# GMM_TESTER_PA_Sheet1.net
KiCad netlist of a schematic drawn in Altium Designer
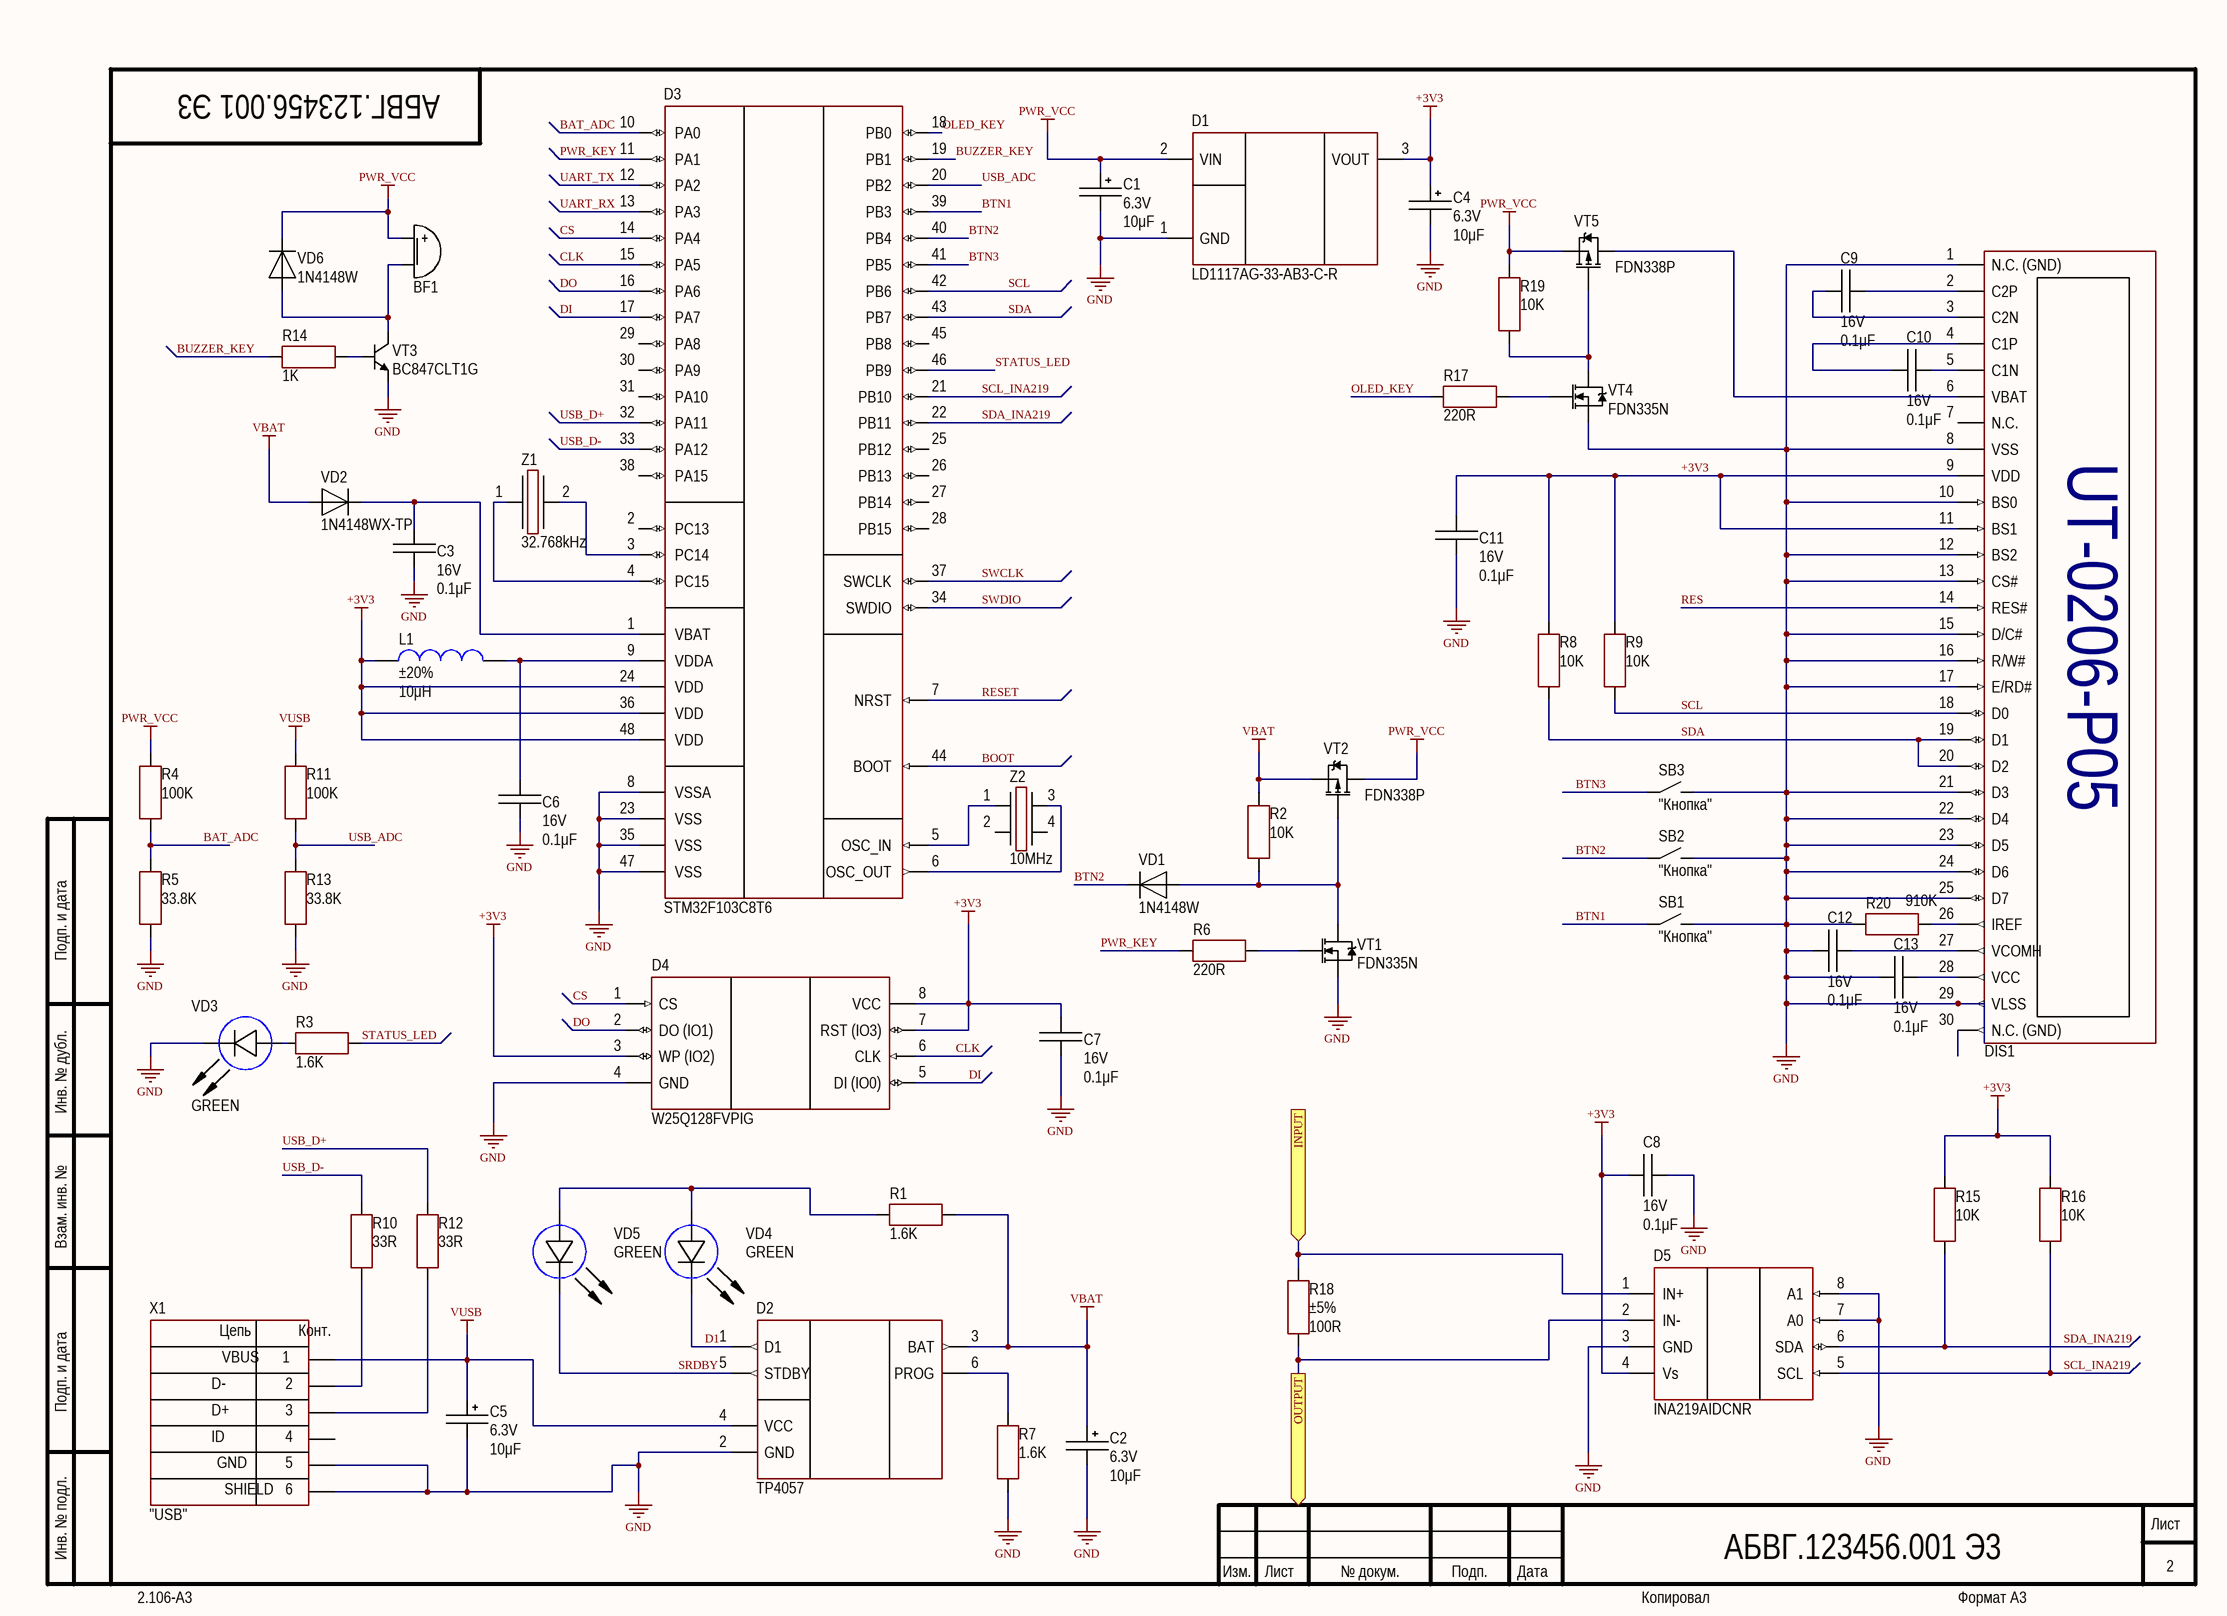
[diagram p0: GMM_TESTER_PA_Sheet1.SchDoc]

(export (version "E")
  (design (tool "Eeschema 10.0.6"))
  (components
    (comp (ref "BF1")
      (value "~")
      (footprint "CustomCase:BUZ: CMT-7525")
      (fields
        (field (name "MANUFACTURER") "PUI Audio")
        (field (name "VALUEMANUFACTURERPARTNUMBER") "DIP switch, 2.73 kHz, 3VDC, 80mA, -20...+70°C")
        (field (name "PARTNUMBER") "AT-0927-TT-6-R")
      )
      (libsource (lib "Electromechanics") (part "Buzzer"))
    )
    (comp (ref "C1")
      (value "10μF")
      (footprint "StandardCase:CAP: TANTAL-A")
      (fields
        (field (name "MANUFACTURER") "AVX")
        (field (name "PARTNUMBER") "F930J107KAAAJ6")
        (field (name "VALUEMANUFACTURERPARTNUMBER") "Tantalum capacitor, 10μF, 6.3V, ±10%, 2Ohm, case A (3216), -55...+125°C")
        (field (name "VOLTAGE") "6.3V")
      )
      (libsource (lib "Capacitor") (part "Tantal_A"))
    )
    (comp (ref "C2")
      (value "10μF")
      (footprint "StandardCase:CAP: TANTAL-A")
      (fields
        (field (name "MANUFACTURER") "AVX")
        (field (name "PARTNUMBER") "F930J107KAAAJ6")
        (field (name "VALUEMANUFACTURERPARTNUMBER") "Tantalum capacitor, 10μF, 6.3V, ±10%, 2Ohm, case A (3216), -55...+125°C")
        (field (name "VOLTAGE") "6.3V")
      )
      (libsource (lib "Capacitor") (part "Tantal_A"))
    )
    (comp (ref "C3")
      (value "0.1μF")
      (footprint "StandardCase:CAP: 0603")
      (fields
        (field (name "MANUFACTURER") "Yageo")
        (field (name "PARTNUMBER") "CC0603KRX7R7BB104")
        (field (name "VALUEMANUFACTURERPARTNUMBER") "Ceramic capacitor, 0.1μF, X7R, ±10%, 16V, 0603, -55...+125°C")
        (field (name "VOLTAGE") "16V")
      )
      (libsource (lib "Capacitor") (part "Ceramic_0603"))
    )
    (comp (ref "C4")
      (value "10μF")
      (footprint "StandardCase:CAP: TANTAL-A")
      (fields
        (field (name "MANUFACTURER") "AVX")
        (field (name "PARTNUMBER") "F930J107KAAAJ6")
        (field (name "VALUEMANUFACTURERPARTNUMBER") "Tantalum capacitor, 10μF, 6.3V, ±10%, 2Ohm, case A (3216), -55...+125°C")
        (field (name "VOLTAGE") "6.3V")
      )
      (libsource (lib "Capacitor") (part "Tantal_A"))
    )
    (comp (ref "C5")
      (value "10μF")
      (footprint "StandardCase:CAP: TANTAL-A")
      (fields
        (field (name "MANUFACTURER") "AVX")
        (field (name "PARTNUMBER") "F930J107KAAAJ6")
        (field (name "VALUEMANUFACTURERPARTNUMBER") "Tantalum capacitor, 10μF, 6.3V, ±10%, 2Ohm, case A (3216), -55...+125°C")
        (field (name "VOLTAGE") "6.3V")
      )
      (libsource (lib "Capacitor") (part "Tantal_A"))
    )
    (comp (ref "C6")
      (value "0.1μF")
      (footprint "StandardCase:CAP: 0603")
      (fields
        (field (name "MANUFACTURER") "Yageo")
        (field (name "PARTNUMBER") "CC0603KRX7R7BB104")
        (field (name "VALUEMANUFACTURERPARTNUMBER") "Ceramic capacitor, 0.1μF, X7R, ±10%, 16V, 0603, -55...+125°C")
        (field (name "VOLTAGE") "16V")
      )
      (libsource (lib "Capacitor") (part "Ceramic_0603"))
    )
    (comp (ref "C7")
      (value "0.1μF")
      (footprint "StandardCase:CAP: 0603")
      (fields
        (field (name "MANUFACTURER") "Yageo")
        (field (name "PARTNUMBER") "CC0603KRX7R7BB104")
        (field (name "VALUEMANUFACTURERPARTNUMBER") "Ceramic capacitor, 0.1μF, X7R, ±10%, 16V, 0603, -55...+125°C")
        (field (name "VOLTAGE") "16V")
      )
      (libsource (lib "Capacitor") (part "Ceramic_0603"))
    )
    (comp (ref "C8")
      (value "0.1μF")
      (footprint "StandardCase:CAP: 0603")
      (fields
        (field (name "MANUFACTURER") "Yageo")
        (field (name "PARTNUMBER") "CC0603KRX7R7BB104")
        (field (name "VALUEMANUFACTURERPARTNUMBER") "Ceramic capacitor, 0.1μF, X7R, ±10%, 16V, 0603, -55...+125°C")
        (field (name "VOLTAGE") "16V")
      )
      (libsource (lib "Capacitor") (part "Ceramic_0603"))
    )
    (comp (ref "C9")
      (value "0.1μF")
      (footprint "StandardCase:CAP: 0603")
      (fields
        (field (name "MANUFACTURER") "Yageo")
        (field (name "PARTNUMBER") "CC0603KRX7R7BB104")
        (field (name "VALUEMANUFACTURERPARTNUMBER") "Ceramic capacitor, 0.1μF, X7R, ±10%, 16V, 0603, -55...+125°C")
        (field (name "VOLTAGE") "16V")
      )
      (libsource (lib "Capacitor") (part "Ceramic_0603"))
    )
    (comp (ref "C10")
      (value "0.1μF")
      (footprint "StandardCase:CAP: 0603")
      (fields
        (field (name "MANUFACTURER") "Yageo")
        (field (name "PARTNUMBER") "CC0603KRX7R7BB104")
        (field (name "VALUEMANUFACTURERPARTNUMBER") "Ceramic capacitor, 0.1μF, X7R, ±10%, 16V, 0603, -55...+125°C")
        (field (name "VOLTAGE") "16V")
      )
      (libsource (lib "Capacitor") (part "Ceramic_0603"))
    )
    (comp (ref "C11")
      (value "0.1μF")
      (footprint "StandardCase:CAP: 0603")
      (fields
        (field (name "MANUFACTURER") "Yageo")
        (field (name "PARTNUMBER") "CC0603KRX7R7BB104")
        (field (name "VALUEMANUFACTURERPARTNUMBER") "Ceramic capacitor, 0.1μF, X7R, ±10%, 16V, 0603, -55...+125°C")
        (field (name "VOLTAGE") "16V")
      )
      (libsource (lib "Capacitor") (part "Ceramic_0603"))
    )
    (comp (ref "C12")
      (value "0.1μF")
      (footprint "StandardCase:CAP: 0603")
      (fields
        (field (name "MANUFACTURER") "Yageo")
        (field (name "PARTNUMBER") "CC0603KRX7R7BB104")
        (field (name "VALUEMANUFACTURERPARTNUMBER") "Ceramic capacitor, 0.1μF, X7R, ±10%, 16V, 0603, -55...+125°C")
        (field (name "VOLTAGE") "16V")
      )
      (libsource (lib "Capacitor") (part "Ceramic_0603"))
    )
    (comp (ref "C13")
      (value "0.1μF")
      (footprint "StandardCase:CAP: 0603")
      (fields
        (field (name "MANUFACTURER") "Yageo")
        (field (name "PARTNUMBER") "CC0603KRX7R7BB104")
        (field (name "VALUEMANUFACTURERPARTNUMBER") "Ceramic capacitor, 0.1μF, X7R, ±10%, 16V, 0603, -55...+125°C")
        (field (name "VOLTAGE") "16V")
      )
      (libsource (lib "Capacitor") (part "Ceramic_0603"))
    )
    (comp (ref "D1")
      (value "~")
      (footprint "SOT89")
      (description "Linear voltage regulator")
      (fields
        (field (name "MANUFACTURER") "STMicroelectronics")
        (field (name "VALUEMANUFACTURERPARTNUMBER") "Linear voltage regulator, input 3.9...18V, 0.6V, output 3.3V, 1.2A, -40...+85°C, SOT89")
        (field (name "PARTNUMBER") "LD1117AG-33-AB3-C-R")
      )
      (libsource (lib "IC. Power supply") (part "LD1117AG-33-AB3-C-R"))
    )
    (comp (ref "D2")
      (value "~")
      (footprint "StandardCase:SOT23-6")
      (description "500mA Linear Li-Ion Battery Charger")
      (fields
        (field (name "MANUFACTURER") "Texas Instruments")
        (field (name "VALUEMANUFACTURERPARTNUMBER") "DC/DC push-pull converter, input 2.25...5.5V, 160kHz, , 500ma, -55...+125°C, SOT23-6")
        (field (name "PARTNUMBER") "TP4057")
      )
      (libsource (lib "IC. Power supply") (part "TP4057"))
    )
    (comp (ref "D3")
      (value "~")
      (footprint "StandardCase:48-LQFP")
      (description "Cortex-M3")
      (fields
        (field (name "MANUFACTURER") "STMicroelectronics")
        (field (name "VALUEMANUFACTURERPARTNUMBER") "IC microcontroller, 32-Bit, Cortex-M3, 72MHz, 64KB, 20KB, 2...3.6V, -40...+85°C, 48-LQFP")
        (field (name "PARTNUMBER") "STM32F103C8T6")
      )
      (libsource (lib "IC. MCU") (part "STM32F103C8T6"))
    )
    (comp (ref "D4")
      (value "~")
      (footprint "StandardCase:8-SOIC")
      (description "FLASH")
      (fields
        (field (name "MANUFACTURER") "Winbond Electronics")
        (field (name "VALUEMANUFACTURERPARTNUMBER") "IC memory, FLASH, 128Mb (16M x 8), 104 MHz, SPI/QuadSPI, 2.7...3.6V, -40...+85°C, 8-WSON")
        (field (name "PARTNUMBER") "W25Q128FVPIG")
      )
      (libsource (lib "IC. Memory") (part "W25Q128FVPIG"))
    )
    (comp (ref "D5")
      (value "~")
      (footprint "SOT23-8")
      (description "Current monitor")
      (fields
        (field (name "MANUFACTURER") "Texas Instruments")
        (field (name "VALUEMANUFACTURERPARTNUMBER") "IC current monitor, ±3%, 350 kHz, 2.7...5.5V, -40...+125°C, SOT23-6")
        (field (name "PARTNUMBER") "INA219AIDCNR")
      )
      (libsource (lib "IC. Sensor") (part "INA219AIDCNR"))
    )
    (comp (ref "DIS1")
      (value "~")
      (footprint "DISP: OLED UT-0206-P05")
      (fields
        (field (name "MANUFACTURER") "Shenzhen Allvision Tech")
        (field (name "VALUEMANUFACTURERPARTNUMBER") "QG-2864KSWEG01, , 5VDC, , -40...+85°C")
      )
      (libsource (lib "Displays") (part "QG-2864KSWEG01"))
    )
    (comp (ref "L1")
      (value "10μH")
      (footprint "StandardCase:IND: 0603")
      (fields
        (field (name "MANUFACTURER") "Murata Electronics")
        (field (name "PARTNUMBER") "LQM18FN100M00D")
        (field (name "VALUEMANUFACTURERPARTNUMBER") "Fixed inductor, 10μH, ±20%, 0603, 50mA, -55...+125°C")
        (field (name "TOLERANCE") "±20%")
      )
      (libsource (lib "Inductor") (part "Inductor_0603"))
    )
    (comp (ref "R1")
      (value "1.6K")
      (footprint "StandardCase:RES: 0603")
      (fields
        (field (name "MANUFACTURER") "Yageo")
        (field (name "PARTNUMBER") "RC0603JR-07100RL")
        (field (name "VALUEMANUFACTURERPARTNUMBER") "Resistor film, 1.6K, , 0603, 0.1W, -55...+125°C")
      )
      (libsource (lib "Resistor") (part "Resistor_0603"))
    )
    (comp (ref "R2")
      (value "10K")
      (footprint "StandardCase:RES: 0603")
      (fields
        (field (name "MANUFACTURER") "Yageo")
        (field (name "PARTNUMBER") "RC0603JR-07100RL")
        (field (name "VALUEMANUFACTURERPARTNUMBER") "Resistor film, 10K, , 0603, 0.1W, -55...+125°C")
      )
      (libsource (lib "") (part "Resistor_0603_1"))
    )
    (comp (ref "R3")
      (value "1.6K")
      (footprint "StandardCase:RES: 0603")
      (fields
        (field (name "MANUFACTURER") "Yageo")
        (field (name "PARTNUMBER") "RC0603JR-07100RL")
        (field (name "VALUEMANUFACTURERPARTNUMBER") "Resistor film, 1.6K, , 0603, 0.1W, -55...+125°C")
      )
      (libsource (lib "Resistor") (part "Resistor_0603"))
    )
    (comp (ref "R4")
      (value "100K")
      (footprint "StandardCase:RES: 0603")
      (fields
        (field (name "MANUFACTURER") "Yageo")
        (field (name "PARTNUMBER") "RC0603JR-07100RL")
        (field (name "VALUEMANUFACTURERPARTNUMBER") "Resistor film, 100K, , 0603, 0.1W, -55...+125°C")
      )
      (libsource (lib "") (part "Resistor_0603_1"))
    )
    (comp (ref "R5")
      (value "33.8K")
      (footprint "StandardCase:RES: 0603")
      (fields
        (field (name "MANUFACTURER") "Yageo")
        (field (name "PARTNUMBER") "RC0603JR-07100RL")
        (field (name "VALUEMANUFACTURERPARTNUMBER") "Resistor film, 33.8K, , 0603, 0.1W, -55...+125°C")
      )
      (libsource (lib "") (part "Resistor_0603_1"))
    )
    (comp (ref "R6")
      (value "220R")
      (footprint "StandardCase:RES: 0603")
      (fields
        (field (name "MANUFACTURER") "Yageo")
        (field (name "PARTNUMBER") "RC0603JR-07100RL")
        (field (name "VALUEMANUFACTURERPARTNUMBER") "Resistor film, 220R, , 0603, 0.1W, -55...+125°C")
      )
      (libsource (lib "Resistor") (part "Resistor_0603"))
    )
    (comp (ref "R7")
      (value "1.6K")
      (footprint "StandardCase:RES: 0603")
      (fields
        (field (name "MANUFACTURER") "Yageo")
        (field (name "PARTNUMBER") "RC0603JR-07100RL")
        (field (name "VALUEMANUFACTURERPARTNUMBER") "Resistor film, 1.6K, , 0603, 0.1W, -55...+125°C")
      )
      (libsource (lib "") (part "Resistor_0603_1"))
    )
    (comp (ref "R8")
      (value "10K")
      (footprint "StandardCase:RES: 0603")
      (fields
        (field (name "MANUFACTURER") "Yageo")
        (field (name "PARTNUMBER") "RC0603JR-07100RL")
        (field (name "VALUEMANUFACTURERPARTNUMBER") "Resistor film, 10K, , 0603, 0.1W, -55...+125°C")
      )
      (libsource (lib "") (part "Resistor_0603_1"))
    )
    (comp (ref "R9")
      (value "10K")
      (footprint "StandardCase:RES: 0603")
      (fields
        (field (name "MANUFACTURER") "Yageo")
        (field (name "PARTNUMBER") "RC0603JR-07100RL")
        (field (name "VALUEMANUFACTURERPARTNUMBER") "Resistor film, 10K, , 0603, 0.1W, -55...+125°C")
      )
      (libsource (lib "") (part "Resistor_0603_1"))
    )
    (comp (ref "R10")
      (value "33R")
      (footprint "StandardCase:RES: 0603")
      (fields
        (field (name "MANUFACTURER") "Yageo")
        (field (name "PARTNUMBER") "RC0603JR-07100RL")
        (field (name "VALUEMANUFACTURERPARTNUMBER") "Resistor film, 33R, , 0603, 0.1W, -55...+125°C")
      )
      (libsource (lib "") (part "Resistor_0603_1"))
    )
    (comp (ref "R11")
      (value "100K")
      (footprint "StandardCase:RES: 0603")
      (fields
        (field (name "MANUFACTURER") "Yageo")
        (field (name "PARTNUMBER") "RC0603JR-07100RL")
        (field (name "VALUEMANUFACTURERPARTNUMBER") "Resistor film, 100K, , 0603, 0.1W, -55...+125°C")
      )
      (libsource (lib "") (part "Resistor_0603_1"))
    )
    (comp (ref "R12")
      (value "33R")
      (footprint "StandardCase:RES: 0603")
      (fields
        (field (name "MANUFACTURER") "Yageo")
        (field (name "PARTNUMBER") "RC0603JR-07100RL")
        (field (name "VALUEMANUFACTURERPARTNUMBER") "Resistor film, 33R, , 0603, 0.1W, -55...+125°C")
      )
      (libsource (lib "") (part "Resistor_0603_1"))
    )
    (comp (ref "R13")
      (value "33.8K")
      (footprint "StandardCase:RES: 0603")
      (fields
        (field (name "MANUFACTURER") "Yageo")
        (field (name "PARTNUMBER") "RC0603JR-07100RL")
        (field (name "VALUEMANUFACTURERPARTNUMBER") "Resistor film, 33.8K, , 0603, 0.1W, -55...+125°C")
      )
      (libsource (lib "") (part "Resistor_0603_1"))
    )
    (comp (ref "R14")
      (value "1K")
      (footprint "StandardCase:RES: 0603")
      (fields
        (field (name "MANUFACTURER") "Yageo")
        (field (name "PARTNUMBER") "RC0603JR-07100RL")
        (field (name "VALUEMANUFACTURERPARTNUMBER") "Resistor film, 1K, , 0603, 0.1W, -55...+125°C")
      )
      (libsource (lib "Resistor") (part "Resistor_0603"))
    )
    (comp (ref "R15")
      (value "10K")
      (footprint "StandardCase:RES: 0603")
      (fields
        (field (name "MANUFACTURER") "Yageo")
        (field (name "PARTNUMBER") "RC0603JR-07100RL")
        (field (name "VALUEMANUFACTURERPARTNUMBER") "Resistor film, 10K, , 0603, 0.1W, -55...+125°C")
      )
      (libsource (lib "") (part "Resistor_0603_1"))
    )
    (comp (ref "R16")
      (value "10K")
      (footprint "StandardCase:RES: 0603")
      (fields
        (field (name "MANUFACTURER") "Yageo")
        (field (name "PARTNUMBER") "RC0603JR-07100RL")
        (field (name "VALUEMANUFACTURERPARTNUMBER") "Resistor film, 10K, , 0603, 0.1W, -55...+125°C")
      )
      (libsource (lib "") (part "Resistor_0603_1"))
    )
    (comp (ref "R17")
      (value "220R")
      (footprint "StandardCase:RES: 0603")
      (fields
        (field (name "MANUFACTURER") "Yageo")
        (field (name "PARTNUMBER") "RC0603JR-07100RL")
        (field (name "VALUEMANUFACTURERPARTNUMBER") "Resistor film, 220R, , 0603, 0.1W, -55...+125°C")
      )
      (libsource (lib "Resistor") (part "Resistor_0603"))
    )
    (comp (ref "R18")
      (value "100R")
      (footprint "StandardCase:RES: 1206")
      (fields
        (field (name "MANUFACTURER") "Yageo")
        (field (name "PARTNUMBER") "RC1206JR-07100RL")
        (field (name "VALUEMANUFACTURERPARTNUMBER") "Resistor film, 100R, ±5%, 1206, 0.25W, -55...+125°C")
        (field (name "TOLERANCE") "±5%")
      )
      (libsource (lib "Resistor") (part "Resistor_1206"))
    )
    (comp (ref "R19")
      (value "10K")
      (footprint "StandardCase:RES: 0603")
      (fields
        (field (name "MANUFACTURER") "Yageo")
        (field (name "PARTNUMBER") "RC0603JR-07100RL")
        (field (name "VALUEMANUFACTURERPARTNUMBER") "Resistor film, 10K, , 0603, 0.1W, -55...+125°C")
      )
      (libsource (lib "") (part "Resistor_0603_1"))
    )
    (comp (ref "R20")
      (value "910K")
      (footprint "StandardCase:RES: 0603")
      (fields
        (field (name "MANUFACTURER") "Yageo")
        (field (name "PARTNUMBER") "RC0603JR-07100RL")
        (field (name "VALUEMANUFACTURERPARTNUMBER") "Resistor film, 910K, , 0603, 0.1W, -55...+125°C")
      )
      (libsource (lib "") (part "Resistor_0603_2"))
    )
    (comp (ref "SB1")
      (value "~")
      (footprint "BUT: SKQGADE010 - duplicate")
      (fields
        (field (name "MANUFACTURER") "TE Connectivity")
        (field (name "VALUEMANUFACTURERPARTNUMBER") "Tactile button, 6x6mm")
        (field (name "PARTNUMBER") "FSM2JSMAATR")
        (field (name "COMMENTTEXT") "\"Кнопка\"")
      )
      (libsource (lib "Electromechanics") (part "Button_tactile"))
    )
    (comp (ref "SB2")
      (value "~")
      (footprint "BUT: SKQGADE010 - duplicate")
      (fields
        (field (name "MANUFACTURER") "TE Connectivity")
        (field (name "VALUEMANUFACTURERPARTNUMBER") "Tactile button, 6x6mm")
        (field (name "PARTNUMBER") "FSM2JSMAATR")
        (field (name "COMMENTTEXT") "\"Кнопка\"")
      )
      (libsource (lib "Electromechanics") (part "Button_tactile"))
    )
    (comp (ref "SB3")
      (value "~")
      (footprint "BUT: SKQGADE010 - duplicate")
      (fields
        (field (name "MANUFACTURER") "TE Connectivity")
        (field (name "VALUEMANUFACTURERPARTNUMBER") "Tactile button, 6x6mm")
        (field (name "PARTNUMBER") "FSM2JSMAATR")
        (field (name "COMMENTTEXT") "\"Кнопка\"")
      )
      (libsource (lib "Electromechanics") (part "Button_tactile"))
    )
    (comp (ref "VD1")
      (value "~")
      (footprint "DIODE: SOD123")
      (fields
        (field (name "MANUFACTURER") "Micro Commercial")
        (field (name "VALUEMANUFACTURERPARTNUMBER") "Single diode, 75V, 150mA, 1V, 4ns, SOD-323, -55...+150°C")
        (field (name "VOLTAGE") "75V")
        (field (name "PARTNUMBER") "1N4148W")
      )
      (libsource (lib "Diode") (part "Diode_single"))
    )
    (comp (ref "VD2")
      (value "~")
      (footprint "StandardCase:DIODE: SOD123")
      (fields
        (field (name "MANUFACTURER") "Micro Commercial")
        (field (name "VALUEMANUFACTURERPARTNUMBER") "Single diode, 75V, 150mA, 1V, 4ns, SOD-323, -55...+150°C")
        (field (name "VOLTAGE") "75V")
        (field (name "PARTNUMBER") "1N4148WX-TP")
      )
      (libsource (lib "Diode") (part "Diode_single"))
    )
    (comp (ref "VD3")
      (value "~")
      (footprint "LED: 0805R")
      (fields
        (field (name "VALUEMANUFACTURERPARTNUMBER") "LED, Green, *, *, *, -55...+150°C")
        (field (name "COLOR") "GREEN")
      )
      (libsource (lib "Diode") (part "LED_single"))
    )
    (comp (ref "VD4")
      (value "~")
      (footprint "LED: 0805G")
      (fields
        (field (name "VALUEMANUFACTURERPARTNUMBER") "LED, Green, *, *, *, -55...+150°C")
        (field (name "COLOR") "GREEN")
      )
      (libsource (lib "Diode") (part "LED_single"))
    )
    (comp (ref "VD5")
      (value "~")
      (footprint "LED: 0805R")
      (fields
        (field (name "VALUEMANUFACTURERPARTNUMBER") "LED, Green, *, *, *, -55...+150°C")
        (field (name "COLOR") "GREEN")
      )
      (libsource (lib "Diode") (part "LED_single"))
    )
    (comp (ref "VD6")
      (value "~")
      (footprint "DIODE: SOD123")
      (fields
        (field (name "MANUFACTURER") "Micro Commercial")
        (field (name "VALUEMANUFACTURERPARTNUMBER") "Single diode, 75V, 150mA, 1V, 4ns, SOD-323, -55...+150°C")
        (field (name "VOLTAGE") "75V")
        (field (name "PARTNUMBER") "1N4148W")
      )
      (libsource (lib "Diode") (part "Diode_single"))
    )
    (comp (ref "VT1")
      (value "~")
      (footprint "StandardCase:SOT23")
      (fields
        (field (name "MANUFACTURER") "Infineon Technologies")
        (field (name "VALUEMANUFACTURERPARTNUMBER") "MOSFET N-channel transistor, 80V, 7A, 9.1nC, 2.5W, 34mOhm, 756pF, 8-TDSON, -55...+150°C")
        (field (name "PARTNUMBER") "FDN335N")
      )
      (libsource (lib "Transistor") (part "MOSFET_N_132"))
    )
    (comp (ref "VT2")
      (value "~")
      (footprint "StandardCase:SOT23")
      (fields
        (field (name "MANUFACTURER") "Infineon Technologies")
        (field (name "VALUEMANUFACTURERPARTNUMBER") "MOSFET P-channel transistor, 20V, 2.6A, 2.9nC, 2.5W, 135mOhm, 220pF, SOT-23, -55...+150°C")
        (field (name "PARTNUMBER") "FDN338P")
      )
      (libsource (lib "Transistor") (part "MOSFET_P_132"))
    )
    (comp (ref "VT3")
      (value "~")
      (footprint "StandardCase:SOT23")
      (fields
        (field (name "MANUFACTURER") "ON Semiconductor")
        (field (name "VALUEMANUFACTURERPARTNUMBER") "NPN transistor, 45V, 100mA, 100MHz, 300mW, 0.6V, 420, SOT-23, -55...+125°C")
        (field (name "PARTNUMBER") "BC847CLT1G")
      )
      (libsource (lib "Transistor") (part "BJT_NPN_132"))
    )
    (comp (ref "VT4")
      (value "~")
      (footprint "StandardCase:SOT23")
      (fields
        (field (name "MANUFACTURER") "Infineon Technologies")
        (field (name "VALUEMANUFACTURERPARTNUMBER") "MOSFET N-channel transistor, 80V, 7A, 9.1nC, 2.5W, 34mOhm, 756pF, 8-TDSON, -55...+150°C")
        (field (name "PARTNUMBER") "FDN335N")
      )
      (libsource (lib "Transistor") (part "MOSFET_N_132"))
    )
    (comp (ref "VT5")
      (value "~")
      (footprint "StandardCase:SOT23")
      (fields
        (field (name "MANUFACTURER") "Infineon Technologies")
        (field (name "VALUEMANUFACTURERPARTNUMBER") "MOSFET P-channel transistor, 20V, 2.6A, 2.9nC, 2.5W, 135mOhm, 220pF, SOT-23, -55...+150°C")
        (field (name "PARTNUMBER") "FDN338P")
      )
      (libsource (lib "Transistor") (part "MOSFET_P_132"))
    )
    (comp (ref "X1")
      (value "~")
      (footprint "CustomCase:CON: USB micro-A (ZX62-B-5PA)")
      (fields
        (field (name "MANUFACTURER") "Hirose Electric")
        (field (name "VALUEMANUFACTURERPARTNUMBER") "USB micro B")
        (field (name "PARTNUMBER") "ZX62-B-5PA")
        (field (name "COMMENTTEXT") "\"USB\"")
      )
      (libsource (lib "Connector") (part "Connector_USB_micro_B"))
    )
    (comp (ref "Z1")
      (value "~")
      (footprint "OSC: FC - 12M")
      (fields
        (field (name "MANUFACTURER") "Epson")
        (field (name "PARTNUMBER") "FC-135 32.7680KA-A5")
        (field (name "VALUEMANUFACTURERPARTNUMBER") "Crystal, 32.768kHz, 12.5pF, ±20ppm, case 3215, -40...+85°C")
        (field (name "FREQUENCY") "32.768kHz")
      )
      (libsource (lib "Oscilator") (part "Crystal_FC-12M"))
    )
    (comp (ref "Z2")
      (value "~")
      (footprint "CustomCase:OSC: 3225")
      (fields
        (field (name "MANUFACTURER") "Diodes Incorporated")
        (field (name "PARTNUMBER") "FL1000002")
        (field (name "VALUEMANUFACTURERPARTNUMBER") "Crystal, 10MHz, 12pF, ±25ppm, case 3225, -40...+85°C")
        (field (name "FREQUENCY") "10MHz")
      )
      (libsource (lib "Oscilator") (part "Crystal_3225"))
    )
  )
  (nets
    (net (code "1") (name "+3V3") (class "Default")
      (node (ref "C11") (pin "1") (pinfunction "1_1") (pintype "power_in"))
      (node (ref "C4") (pin "1") (pinfunction "1_1") (pintype "power_in"))
      (node (ref "C7") (pin "1") (pinfunction "1_1") (pintype "power_in"))
      (node (ref "C8") (pin "2") (pinfunction "2_2") (pintype "power_in"))
      (node (ref "D1") (pin "3") (pinfunction "VOUT_3") (pintype "power_in"))
      (node (ref "D3") (pin "24") (pinfunction "VDD_24") (pintype "power_in"))
      (node (ref "D3") (pin "36") (pinfunction "VDD_36") (pintype "power_in"))
      (node (ref "D3") (pin "48") (pinfunction "VDD_48") (pintype "power_in"))
      (node (ref "D4") (pin "3") (pinfunction "WP_(IO2)_3") (pintype "bidirectional"))
      (node (ref "D4") (pin "7") (pinfunction "RST_(IO3)_7") (pintype "bidirectional"))
      (node (ref "D4") (pin "8") (pinfunction "VCC_8") (pintype "power_in"))
      (node (ref "D5") (pin "4") (pinfunction "Vs_4") (pintype "passive"))
      (node (ref "DIS1") (pin "11") (pinfunction "BS1_11") (pintype "input"))
      (node (ref "DIS1") (pin "9") (pinfunction "VDD_9") (pintype "power_in"))
      (node (ref "L1") (pin "2") (pinfunction "2_2") (pintype "passive"))
      (node (ref "R15") (pin "2") (pinfunction "2_2") (pintype "passive"))
      (node (ref "R16") (pin "2") (pinfunction "2_2") (pintype "passive"))
      (node (ref "R8") (pin "2") (pinfunction "2_2") (pintype "passive"))
      (node (ref "R9") (pin "2") (pinfunction "2_2") (pintype "passive"))
    )
    (net (code "2") (name "/BAT_ADC") (class "Default")
      (node (ref "D3") (pin "10") (pinfunction "PA0_10") (pintype "bidirectional"))
      (node (ref "R4") (pin "1") (pinfunction "1_1") (pintype "passive"))
      (node (ref "R5") (pin "2") (pinfunction "2_2") (pintype "passive"))
    )
    (net (code "3") (name "/BOOT") (class "Default")
      (node (ref "D3") (pin "44") (pinfunction "BOOT_44") (pintype "input"))
    )
    (net (code "4") (name "/BTN1") (class "Default")
      (node (ref "D3") (pin "39") (pinfunction "PB3_39") (pintype "bidirectional"))
      (node (ref "SB1") (pin "1") (pinfunction "1_1") (pintype "passive"))
    )
    (net (code "5") (name "/BTN2") (class "Default")
      (node (ref "D3") (pin "40") (pinfunction "PB4_40") (pintype "bidirectional"))
      (node (ref "SB2") (pin "1") (pinfunction "1_1") (pintype "passive"))
      (node (ref "VD1") (pin "2") (pinfunction "2_2") (pintype "passive"))
    )
    (net (code "6") (name "/BTN3") (class "Default")
      (node (ref "D3") (pin "41") (pinfunction "PB5_41") (pintype "bidirectional"))
      (node (ref "SB3") (pin "1") (pinfunction "1_1") (pintype "passive"))
    )
    (net (code "7") (name "/BUZZER_KEY") (class "Default")
      (node (ref "D3") (pin "19") (pinfunction "PB1_19") (pintype "bidirectional"))
      (node (ref "R14") (pin "2") (pinfunction "2_2") (pintype "passive"))
    )
    (net (code "8") (name "/CLK") (class "Default")
      (node (ref "D3") (pin "15") (pinfunction "PA5_15") (pintype "bidirectional"))
      (node (ref "D4") (pin "6") (pinfunction "CLK_6") (pintype "input"))
    )
    (net (code "9") (name "/CS") (class "Default")
      (node (ref "D3") (pin "14") (pinfunction "PA4_14") (pintype "bidirectional"))
      (node (ref "D4") (pin "1") (pinfunction "CS_1") (pintype "input"))
    )
    (net (code "10") (name "/D1") (class "Default")
      (node (ref "D2") (pin "1") (pinfunction "D1_1") (pintype "output"))
      (node (ref "VD4") (pin "2") (pinfunction "C_2") (pintype "passive"))
    )
    (net (code "11") (name "/DI") (class "Default")
      (node (ref "D3") (pin "17") (pinfunction "PA7_17") (pintype "bidirectional"))
      (node (ref "D4") (pin "5") (pinfunction "DI_(IO0)_5") (pintype "bidirectional"))
    )
    (net (code "12") (name "/DO") (class "Default")
      (node (ref "D3") (pin "16") (pinfunction "PA6_16") (pintype "bidirectional"))
      (node (ref "D4") (pin "2") (pinfunction "DO_(IO1)_2") (pintype "bidirectional"))
    )
    (net (code "13") (name "/INPUT") (class "Default")
      (node (ref "D5") (pin "1") (pinfunction "IN+_1") (pintype "passive"))
      (node (ref "R18") (pin "2") (pinfunction "2_2") (pintype "passive"))
    )
    (net (code "14") (name "/OLED_KEY") (class "Default")
      (node (ref "D3") (pin "18") (pinfunction "PB0_18") (pintype "bidirectional"))
      (node (ref "R17") (pin "2") (pinfunction "2_2") (pintype "passive"))
    )
    (net (code "15") (name "/OUTPUT") (class "Default")
      (node (ref "D5") (pin "2") (pinfunction "IN-_2") (pintype "passive"))
      (node (ref "R18") (pin "1") (pinfunction "1_1") (pintype "passive"))
    )
    (net (code "16") (name "/PWR_KEY") (class "Default")
      (node (ref "D3") (pin "11") (pinfunction "PA1_11") (pintype "bidirectional"))
      (node (ref "R6") (pin "2") (pinfunction "2_2") (pintype "passive"))
    )
    (net (code "17") (name "/RES") (class "Default")
      (node (ref "DIS1") (pin "14") (pinfunction "RES#_14") (pintype "input"))
    )
    (net (code "18") (name "/RESET") (class "Default")
      (node (ref "D3") (pin "7") (pinfunction "NRST_7") (pintype "input"))
    )
    (net (code "19") (name "/SCL") (class "Default")
      (node (ref "D3") (pin "42") (pinfunction "PB6_42") (pintype "bidirectional"))
      (node (ref "DIS1") (pin "18") (pinfunction "D0_18") (pintype "bidirectional"))
      (node (ref "R9") (pin "1") (pinfunction "1_1") (pintype "passive"))
    )
    (net (code "20") (name "/SCL_INA219") (class "Default")
      (node (ref "D3") (pin "21") (pinfunction "PB10_21") (pintype "bidirectional"))
      (node (ref "D5") (pin "5") (pinfunction "SCL_5") (pintype "input"))
      (node (ref "R16") (pin "1") (pinfunction "1_1") (pintype "passive"))
    )
    (net (code "21") (name "/SDA") (class "Default")
      (node (ref "D3") (pin "43") (pinfunction "PB7_43") (pintype "bidirectional"))
      (node (ref "DIS1") (pin "19") (pinfunction "D1_19") (pintype "bidirectional"))
      (node (ref "DIS1") (pin "20") (pinfunction "D2_20") (pintype "bidirectional"))
      (node (ref "R8") (pin "1") (pinfunction "1_1") (pintype "passive"))
    )
    (net (code "22") (name "/SDA_INA219") (class "Default")
      (node (ref "D3") (pin "22") (pinfunction "PB11_22") (pintype "bidirectional"))
      (node (ref "D5") (pin "6") (pinfunction "SDA_6") (pintype "bidirectional"))
      (node (ref "R15") (pin "1") (pinfunction "1_1") (pintype "passive"))
    )
    (net (code "23") (name "/SRDBY") (class "Default")
      (node (ref "D2") (pin "5") (pinfunction "STDBY_5") (pintype "output"))
      (node (ref "VD5") (pin "2") (pinfunction "C_2") (pintype "passive"))
    )
    (net (code "24") (name "/STATUS_LED") (class "Default")
      (node (ref "D3") (pin "46") (pinfunction "PB9_46") (pintype "bidirectional"))
      (node (ref "R3") (pin "1") (pinfunction "1_1") (pintype "passive"))
    )
    (net (code "25") (name "/SWCLK") (class "Default")
      (node (ref "D3") (pin "37") (pinfunction "SWCLK_37") (pintype "bidirectional"))
    )
    (net (code "26") (name "/SWDIO") (class "Default")
      (node (ref "D3") (pin "34") (pinfunction "SWDIO_34") (pintype "bidirectional"))
    )
    (net (code "27") (name "/UART_RX") (class "Default")
      (node (ref "D3") (pin "13") (pinfunction "PA3_13") (pintype "bidirectional"))
    )
    (net (code "28") (name "/UART_TX") (class "Default")
      (node (ref "D3") (pin "12") (pinfunction "PA2_12") (pintype "bidirectional"))
    )
    (net (code "29") (name "/USB_ADC") (class "Default")
      (node (ref "D3") (pin "20") (pinfunction "PB2_20") (pintype "bidirectional"))
      (node (ref "R11") (pin "1") (pinfunction "1_1") (pintype "passive"))
      (node (ref "R13") (pin "2") (pinfunction "2_2") (pintype "passive"))
    )
    (net (code "30") (name "/USB_D+") (class "Default")
      (node (ref "D3") (pin "32") (pinfunction "PA11_32") (pintype "bidirectional"))
      (node (ref "R12") (pin "2") (pinfunction "2_2") (pintype "passive"))
    )
    (net (code "31") (name "/USB_D-") (class "Default")
      (node (ref "D3") (pin "33") (pinfunction "PA12_33") (pintype "bidirectional"))
      (node (ref "R10") (pin "2") (pinfunction "2_2") (pintype "passive"))
    )
    (net (code "32") (name "GND") (class "Default")
      (node (ref "C1") (pin "2") (pinfunction "2_2") (pintype "power_in"))
      (node (ref "C11") (pin "2") (pinfunction "2_2") (pintype "power_in"))
      (node (ref "C12") (pin "2") (pinfunction "2_2") (pintype "power_in"))
      (node (ref "C13") (pin "2") (pinfunction "2_2") (pintype "power_in"))
      (node (ref "C2") (pin "2") (pinfunction "2_2") (pintype "power_in"))
      (node (ref "C3") (pin "2") (pinfunction "2_2") (pintype "power_in"))
      (node (ref "C4") (pin "2") (pinfunction "2_2") (pintype "power_in"))
      (node (ref "C5") (pin "2") (pinfunction "2_2") (pintype "power_in"))
      (node (ref "C6") (pin "2") (pinfunction "2_2") (pintype "power_in"))
      (node (ref "C7") (pin "2") (pinfunction "2_2") (pintype "power_in"))
      (node (ref "C8") (pin "1") (pinfunction "1_1") (pintype "power_in"))
      (node (ref "D1") (pin "1") (pinfunction "GND_1") (pintype "power_in"))
      (node (ref "D2") (pin "2") (pinfunction "GND_2") (pintype "passive"))
      (node (ref "D3") (pin "23") (pinfunction "VSS_23") (pintype "power_in"))
      (node (ref "D3") (pin "35") (pinfunction "VSS_35") (pintype "power_in"))
      (node (ref "D3") (pin "47") (pinfunction "VSS_47") (pintype "power_in"))
      (node (ref "D3") (pin "8") (pinfunction "VSSA_8") (pintype "power_in"))
      (node (ref "D4") (pin "4") (pinfunction "GND_4") (pintype "power_in"))
      (node (ref "D5") (pin "3") (pinfunction "GND_3") (pintype "passive"))
      (node (ref "D5") (pin "7") (pinfunction "A0_7") (pintype "input"))
      (node (ref "D5") (pin "8") (pinfunction "A1_8") (pintype "input"))
      (node (ref "DIS1") (pin "1") (pinfunction "N.C._(GND)_1") (pintype "passive"))
      (node (ref "DIS1") (pin "10") (pinfunction "BS0_10") (pintype "input"))
      (node (ref "DIS1") (pin "12") (pinfunction "BS2_12") (pintype "input"))
      (node (ref "DIS1") (pin "13") (pinfunction "CS#_13") (pintype "input"))
      (node (ref "DIS1") (pin "15") (pinfunction "D/C#_15") (pintype "input"))
      (node (ref "DIS1") (pin "16") (pinfunction "R/W#_16") (pintype "input"))
      (node (ref "DIS1") (pin "17") (pinfunction "E/RD#_17") (pintype "input"))
      (node (ref "DIS1") (pin "21") (pinfunction "D3_21") (pintype "bidirectional"))
      (node (ref "DIS1") (pin "22") (pinfunction "D4_22") (pintype "bidirectional"))
      (node (ref "DIS1") (pin "23") (pinfunction "D5_23") (pintype "bidirectional"))
      (node (ref "DIS1") (pin "24") (pinfunction "D6_24") (pintype "bidirectional"))
      (node (ref "DIS1") (pin "25") (pinfunction "D7_25") (pintype "bidirectional"))
      (node (ref "DIS1") (pin "29") (pinfunction "VLSS_29") (pintype "output"))
      (node (ref "DIS1") (pin "8") (pinfunction "VSS_8") (pintype "passive"))
      (node (ref "R13") (pin "1") (pinfunction "1_1") (pintype "passive"))
      (node (ref "R20") (pin "1") (pinfunction "1_1") (pintype "passive"))
      (node (ref "R5") (pin "1") (pinfunction "1_1") (pintype "passive"))
      (node (ref "R7") (pin "1") (pinfunction "1_1") (pintype "passive"))
      (node (ref "SB1") (pin "2") (pinfunction "2_2") (pintype "passive"))
      (node (ref "SB2") (pin "2") (pinfunction "2_2") (pintype "passive"))
      (node (ref "SB3") (pin "2") (pinfunction "2_2") (pintype "passive"))
      (node (ref "VD3") (pin "2") (pinfunction "C_2") (pintype "passive"))
      (node (ref "VT1") (pin "2") (pinfunction "S_2") (pintype "passive"))
      (node (ref "VT3") (pin "2") (pinfunction "E_2") (pintype "passive"))
      (node (ref "VT4") (pin "2") (pinfunction "S_2") (pintype "passive"))
      (node (ref "X1") (pin "0") (pinfunction "0_0") (pintype "passive"))
      (node (ref "X1") (pin "5") (pinfunction "5_5") (pintype "passive"))
    )
    (net (code "33") (name "Net-(BF1--)") (class "Default")
      (node (ref "BF1") (pin "2") (pinfunction "-_2") (pintype "passive"))
      (node (ref "VD6") (pin "1") (pinfunction "1_1") (pintype "passive"))
      (node (ref "VT3") (pin "3") (pinfunction "C_3") (pintype "passive"))
    )
    (net (code "34") (name "Net-(D2-PROG)") (class "Default")
      (node (ref "D2") (pin "6") (pinfunction "PROG_6") (pintype "power_in"))
      (node (ref "R7") (pin "2") (pinfunction "2_2") (pintype "passive"))
    )
    (net (code "35") (name "Net-(D3-OSC_IN)") (class "Default")
      (node (ref "D3") (pin "5") (pinfunction "OSC_IN_5") (pintype "input"))
      (node (ref "Z2") (pin "1") (pinfunction "1_1") (pintype "passive"))
    )
    (net (code "36") (name "Net-(D3-OSC_OUT)") (class "Default")
      (node (ref "D3") (pin "6") (pinfunction "OSC_OUT_6") (pintype "output"))
      (node (ref "Z2") (pin "3") (pinfunction "3_3") (pintype "passive"))
    )
    (net (code "37") (name "Net-(D3-PC14)") (class "Default")
      (node (ref "D3") (pin "3") (pinfunction "PC14_3") (pintype "bidirectional"))
      (node (ref "Z1") (pin "2") (pinfunction "2_2") (pintype "passive"))
    )
    (net (code "38") (name "Net-(D3-PC15)") (class "Default")
      (node (ref "D3") (pin "4") (pinfunction "PC15_4") (pintype "bidirectional"))
      (node (ref "Z1") (pin "1") (pinfunction "1_1") (pintype "passive"))
    )
    (net (code "39") (name "Net-(D3-VBAT)") (class "Default")
      (node (ref "C3") (pin "1") (pinfunction "1_1") (pintype "power_in"))
      (node (ref "D3") (pin "1") (pinfunction "VBAT_1") (pintype "power_in"))
      (node (ref "VD2") (pin "2") (pinfunction "2_2") (pintype "passive"))
    )
    (net (code "40") (name "Net-(D3-VDDA)") (class "Default")
      (node (ref "C6") (pin "1") (pinfunction "1_1") (pintype "power_in"))
      (node (ref "D3") (pin "9") (pinfunction "VDDA_9") (pintype "power_in"))
      (node (ref "L1") (pin "1") (pinfunction "1_1") (pintype "passive"))
    )
    (net (code "41") (name "Net-(DIS1-C1N)") (class "Default")
      (node (ref "C10") (pin "1") (pinfunction "1_1") (pintype "power_in"))
      (node (ref "DIS1") (pin "5") (pinfunction "C1N_5") (pintype "passive"))
    )
    (net (code "42") (name "Net-(DIS1-C1P)") (class "Default")
      (node (ref "C10") (pin "2") (pinfunction "2_2") (pintype "power_in"))
      (node (ref "DIS1") (pin "4") (pinfunction "C1P_4") (pintype "power_in"))
    )
    (net (code "43") (name "Net-(DIS1-C2N)") (class "Default")
      (node (ref "C9") (pin "2") (pinfunction "2_2") (pintype "power_in"))
      (node (ref "DIS1") (pin "3") (pinfunction "C2N_3") (pintype "passive"))
    )
    (net (code "44") (name "Net-(DIS1-C2P)") (class "Default")
      (node (ref "C9") (pin "1") (pinfunction "1_1") (pintype "power_in"))
      (node (ref "DIS1") (pin "2") (pinfunction "C2P_2") (pintype "power_in"))
    )
    (net (code "45") (name "Net-(DIS1-IREF)") (class "Default")
      (node (ref "DIS1") (pin "26") (pinfunction "IREF_26") (pintype "output"))
      (node (ref "R20") (pin "2") (pinfunction "2_2") (pintype "passive"))
    )
    (net (code "46") (name "Net-(DIS1-VBAT)") (class "Default")
      (node (ref "DIS1") (pin "6") (pinfunction "VBAT_6") (pintype "power_in"))
      (node (ref "VT5") (pin "3") (pinfunction "D_3") (pintype "passive"))
    )
    (net (code "47") (name "Net-(DIS1-VCC)") (class "Default")
      (node (ref "C13") (pin "1") (pinfunction "1_1") (pintype "power_in"))
      (node (ref "DIS1") (pin "28") (pinfunction "VCC_28") (pintype "output"))
    )
    (net (code "48") (name "Net-(DIS1-VCOMH)") (class "Default")
      (node (ref "C12") (pin "1") (pinfunction "1_1") (pintype "power_in"))
      (node (ref "DIS1") (pin "27") (pinfunction "VCOMH_27") (pintype "output"))
    )
    (net (code "49") (name "Net-(R10-Pad1)") (class "Default")
      (node (ref "R10") (pin "1") (pinfunction "1_1") (pintype "passive"))
      (node (ref "X1") (pin "2") (pinfunction "2_2") (pintype "passive"))
    )
    (net (code "50") (name "Net-(R12-Pad1)") (class "Default")
      (node (ref "R12") (pin "1") (pinfunction "1_1") (pintype "passive"))
      (node (ref "X1") (pin "3") (pinfunction "3_3") (pintype "passive"))
    )
    (net (code "51") (name "Net-(VD3-A)") (class "Default")
      (node (ref "R3") (pin "2") (pinfunction "2_2") (pintype "passive"))
      (node (ref "VD3") (pin "1") (pinfunction "A_1") (pintype "passive"))
    )
    (net (code "52") (name "Net-(VD4-A)") (class "Default")
      (node (ref "R1") (pin "2") (pinfunction "2_2") (pintype "passive"))
      (node (ref "VD4") (pin "1") (pinfunction "A_1") (pintype "passive"))
      (node (ref "VD5") (pin "1") (pinfunction "A_1") (pintype "passive"))
    )
    (net (code "53") (name "Net-(VT1-D)") (class "Default")
      (node (ref "R2") (pin "1") (pinfunction "1_1") (pintype "passive"))
      (node (ref "VD1") (pin "1") (pinfunction "1_1") (pintype "passive"))
      (node (ref "VT1") (pin "3") (pinfunction "D_3") (pintype "passive"))
      (node (ref "VT2") (pin "1") (pinfunction "G_1") (pintype "passive"))
    )
    (net (code "54") (name "Net-(VT1-G)") (class "Default")
      (node (ref "R6") (pin "1") (pinfunction "1_1") (pintype "passive"))
      (node (ref "VT1") (pin "1") (pinfunction "G_1") (pintype "passive"))
    )
    (net (code "55") (name "Net-(VT3-B)") (class "Default")
      (node (ref "R14") (pin "1") (pinfunction "1_1") (pintype "passive"))
      (node (ref "VT3") (pin "1") (pinfunction "B_1") (pintype "passive"))
    )
    (net (code "56") (name "Net-(VT4-D)") (class "Default")
      (node (ref "R19") (pin "1") (pinfunction "1_1") (pintype "passive"))
      (node (ref "VT4") (pin "3") (pinfunction "D_3") (pintype "passive"))
      (node (ref "VT5") (pin "1") (pinfunction "G_1") (pintype "passive"))
    )
    (net (code "57") (name "Net-(VT4-G)") (class "Default")
      (node (ref "R17") (pin "1") (pinfunction "1_1") (pintype "passive"))
      (node (ref "VT4") (pin "1") (pinfunction "G_1") (pintype "passive"))
    )
    (net (code "58") (name "PWR_VCC") (class "Default")
      (node (ref "BF1") (pin "1") (pinfunction "+_1") (pintype "passive"))
      (node (ref "C1") (pin "1") (pinfunction "1_1") (pintype "power_in"))
      (node (ref "D1") (pin "2") (pinfunction "VIN_2") (pintype "power_in"))
      (node (ref "R19") (pin "2") (pinfunction "2_2") (pintype "passive"))
      (node (ref "R4") (pin "2") (pinfunction "2_2") (pintype "passive"))
      (node (ref "VD6") (pin "2") (pinfunction "2_2") (pintype "passive"))
      (node (ref "VT2") (pin "3") (pinfunction "D_3") (pintype "passive"))
      (node (ref "VT5") (pin "2") (pinfunction "S_2") (pintype "passive"))
    )
    (net (code "59") (name "VBAT") (class "Default")
      (node (ref "C2") (pin "1") (pinfunction "1_1") (pintype "power_in"))
      (node (ref "D2") (pin "3") (pinfunction "BAT_3") (pintype "output"))
      (node (ref "R1") (pin "1") (pinfunction "1_1") (pintype "passive"))
      (node (ref "R2") (pin "2") (pinfunction "2_2") (pintype "passive"))
      (node (ref "VD2") (pin "1") (pinfunction "1_1") (pintype "passive"))
      (node (ref "VT2") (pin "2") (pinfunction "S_2") (pintype "passive"))
    )
    (net (code "60") (name "VUSB") (class "Default")
      (node (ref "C5") (pin "1") (pinfunction "1_1") (pintype "power_in"))
      (node (ref "D2") (pin "4") (pinfunction "VCC_4") (pintype "power_in"))
      (node (ref "R11") (pin "2") (pinfunction "2_2") (pintype "passive"))
      (node (ref "X1") (pin "1") (pintype "passive"))
    )
    (net (code "61") (name "unconnected-(D3-PA8-Pad29)") (class "Default")
      (node (ref "D3") (pin "29") (pinfunction "PA8_29") (pintype "bidirectional"))
    )
    (net (code "62") (name "unconnected-(D3-PA9-Pad30)") (class "Default")
      (node (ref "D3") (pin "30") (pinfunction "PA9_30") (pintype "bidirectional"))
    )
    (net (code "63") (name "unconnected-(D3-PA10-Pad31)") (class "Default")
      (node (ref "D3") (pin "31") (pinfunction "PA10_31") (pintype "bidirectional"))
    )
    (net (code "64") (name "unconnected-(D3-PA15-Pad38)") (class "Default")
      (node (ref "D3") (pin "38") (pinfunction "PA15_38") (pintype "bidirectional"))
    )
    (net (code "65") (name "unconnected-(D3-PB8-Pad45)") (class "Default")
      (node (ref "D3") (pin "45") (pinfunction "PB8_45") (pintype "bidirectional"))
    )
    (net (code "66") (name "unconnected-(D3-PB12-Pad25)") (class "Default")
      (node (ref "D3") (pin "25") (pinfunction "PB12_25") (pintype "bidirectional"))
    )
    (net (code "67") (name "unconnected-(D3-PB13-Pad26)") (class "Default")
      (node (ref "D3") (pin "26") (pinfunction "PB13_26") (pintype "bidirectional"))
    )
    (net (code "68") (name "unconnected-(D3-PB14-Pad27)") (class "Default")
      (node (ref "D3") (pin "27") (pinfunction "PB14_27") (pintype "bidirectional"))
    )
    (net (code "69") (name "unconnected-(D3-PB15-Pad28)") (class "Default")
      (node (ref "D3") (pin "28") (pinfunction "PB15_28") (pintype "bidirectional"))
    )
    (net (code "70") (name "unconnected-(D3-PC13-Pad2)") (class "Default")
      (node (ref "D3") (pin "2") (pinfunction "PC13_2") (pintype "bidirectional"))
    )
    (net (code "71") (name "unconnected-(DIS1-N.C.-Pad7)") (class "Default")
      (node (ref "DIS1") (pin "7") (pinfunction "N.C._7") (pintype "passive"))
    )
    (net (code "72") (name "unconnected-(DIS1-N.C._(GND)-Pad30)") (class "Default")
      (node (ref "DIS1") (pin "30") (pinfunction "N.C._(GND)_30") (pintype "output"))
    )
    (net (code "73") (name "unconnected-(X1-Pad4)") (class "Default")
      (node (ref "X1") (pin "4") (pinfunction "4_4") (pintype "passive"))
    )
    (net (code "74") (name "unconnected-(Z2-Pad2)") (class "Default")
      (node (ref "Z2") (pin "2") (pinfunction "2_2") (pintype "passive"))
    )
    (net (code "75") (name "unconnected-(Z2-Pad4)") (class "Default")
      (node (ref "Z2") (pin "4") (pinfunction "4_4") (pintype "passive"))
    )
  )
)
